# CAN.net
KiCad netlist of a schematic drawn in Altium Designer
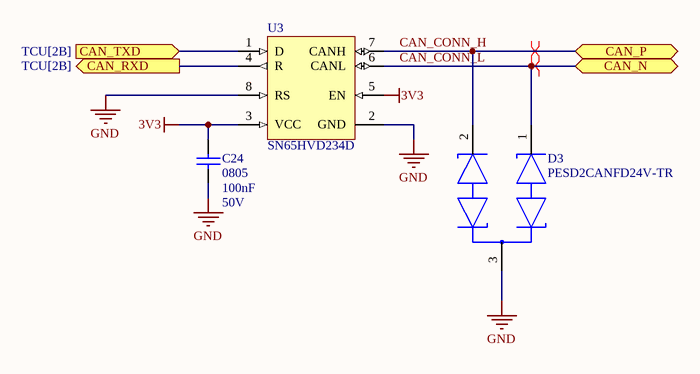
[diagram p0: CAN.SchDoc]

(export (version "E")
  (design (tool "Eeschema 10.0.6"))
  (components
    (comp (ref "C24")
      (value "C0805C104K5RACTU")
      (footprint "CAPC2013X88X50NL20T25")
      (fields
        (field (name "MANUFACTURER") "Kemet")
        (field (name "CASE CODE (IMPERIAL)") "0805")
        (field (name "CAPACITANCE") "100nF")
        (field (name "VOLTAGE RATING") "50V")
        (field (name "TOLERANCE") "10%")
        (field (name "VOLTAGE") "500V")
      )
      (libsource (lib "Altium Content Vault") (part "CAP"))
    )
    (comp (ref "D3")
      (value "PESD2CANFD24V-TR")
      (footprint "FP-SOT23-IPC_A")
      (description "TVS DIODE 24VWM 42VC TO236AB")
      (libsource (lib "Altium Content Vault") (part "e1aa1e71a25486d94450bfc930cdd33"))
    )
    (comp (ref "U3")
      (value "SN65HVD234D")
      (footprint "D0008A_M")
      (fields (field (name "MANUFACTURER") "Texas Instruments"))
      (libsource (lib "Altium Content Vault") (part "TI-SN65HVD234-SOIC_D-8"))
    )
  )
  (nets
    (net (code "1") (name "/CAN_CONN_H") (class "Default")
      (node (ref "D3") (pin "2") (pinfunction "K2_2") (pintype "passive"))
      (node (ref "U3") (pin "7") (pinfunction "CANH_7") (pintype "bidirectional"))
    )
    (net (code "2") (name "/CAN_CONN_L") (class "Default")
      (node (ref "D3") (pin "1") (pinfunction "K1_1") (pintype "passive"))
      (node (ref "U3") (pin "6") (pinfunction "CANL_6") (pintype "bidirectional"))
    )
    (net (code "3") (name "/CAN_RXD") (class "Default")
      (node (ref "U3") (pin "4") (pinfunction "R_4") (pintype "output"))
    )
    (net (code "4") (name "/CAN_TXD") (class "Default")
      (node (ref "U3") (pin "1") (pinfunction "D_1") (pintype "input"))
    )
    (net (code "5") (name "3V3") (class "Default")
      (node (ref "C24") (pin "1") (pinfunction "1_1") (pintype "passive"))
      (node (ref "U3") (pin "3") (pinfunction "VCC_3") (pintype "input"))
      (node (ref "U3") (pin "5") (pinfunction "EN_5") (pintype "input"))
    )
    (net (code "6") (name "GND") (class "Default")
      (node (ref "C24") (pin "2") (pinfunction "2_2") (pintype "passive"))
      (node (ref "D3") (pin "3") (pinfunction "CC_3") (pintype "passive"))
      (node (ref "U3") (pin "2") (pinfunction "GND_2") (pintype "power_in"))
      (node (ref "U3") (pin "8") (pinfunction "RS_8") (pintype "input"))
    )
  )
)
